# DRS4.net
KiCad netlist of a schematic drawn in Altium Designer
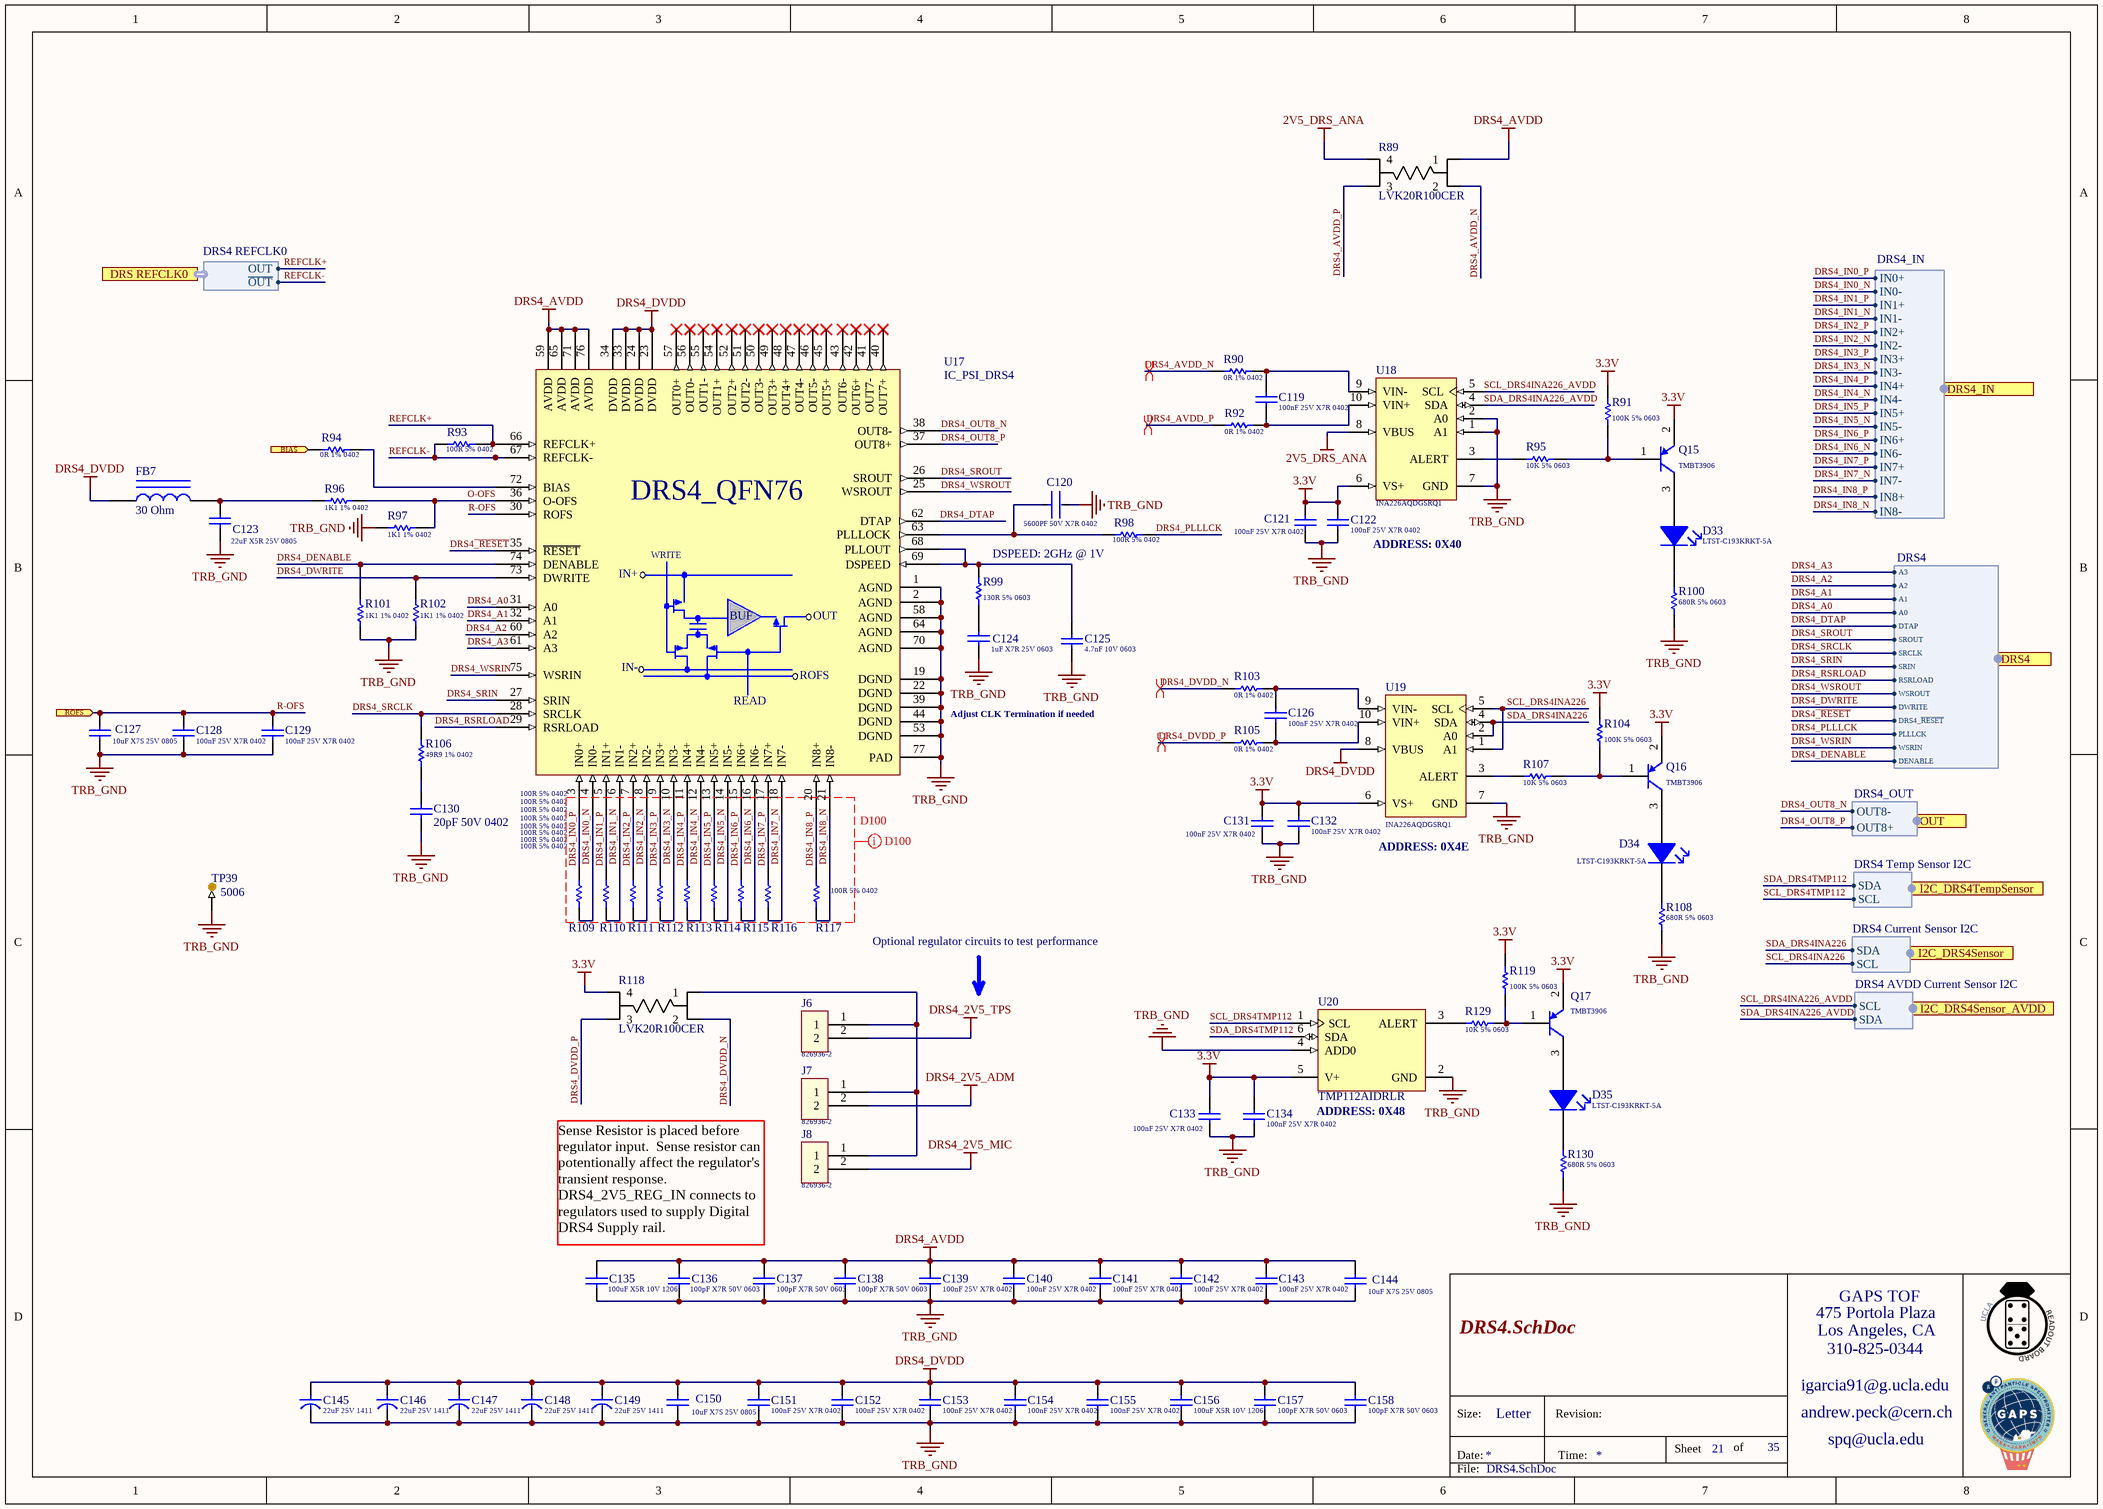
[diagram p0: DRS4.SchDoc]

(export (version "E")
  (design (tool "Eeschema 10.0.6"))
  (components
    (comp (ref "C119")
      (value "Cap_Taiyo_Yuden_TMK105B7104KV-FR_100nF")
      (footprint "Cap_Taiyo_Yuden_TMK105B7104KV-FR_100nF")
      (description "CAP CER 100nF 25V X7R 0402")
      (fields (field (name "CAPACITANCE") "100nF 25V X7R 0402"))
      (libsource (lib "Cap_Taiyo_Yuden_TMK105B7104KV-FR_100nF") (part "Cap_Taiyo_Yuden_TMK105B7104KV-FR_100nF"))
    )
    (comp (ref "C120")
      (value "5600PF 50V X7R 0402")
      (footprint "FP-C0402-BB-MFG")
      (description "CAP CER 5600PF 50V X7R 0402\r\nC0402C562K5RACTU")
      (fields (field (name "TOLERANCE") "0.1") (field (name "MANUFACTURER") "Kemet"))
      (libsource (lib "Altium Content Vault") (part "b4654b650e69147ec39a6b967a45e02"))
    )
    (comp (ref "C121")
      (value "Cap_Taiyo_Yuden_TMK105B7104KV-FR_100nF")
      (footprint "Cap_Taiyo_Yuden_TMK105B7104KV-FR_100nF")
      (description "CAP CER 100nF 25V X7R 0402")
      (fields (field (name "CAPACITANCE") "100nF 25V X7R 0402"))
      (libsource (lib "Cap_Taiyo_Yuden_TMK105B7104KV-FR_100nF") (part "Cap_Taiyo_Yuden_TMK105B7104KV-FR_100nF"))
    )
    (comp (ref "C122")
      (value "Cap_Taiyo_Yuden_TMK105B7104KV-FR_100nF")
      (footprint "Cap_Taiyo_Yuden_TMK105B7104KV-FR_100nF")
      (description "CAP CER 100nF 25V X7R 0402")
      (fields (field (name "CAPACITANCE") "100nF 25V X7R 0402"))
      (libsource (lib "Cap_Taiyo_Yuden_TMK105B7104KV-FR_100nF") (part "Cap_Taiyo_Yuden_TMK105B7104KV-FR_100nF"))
    )
    (comp (ref "C123")
      (value "Cap_Murata_GRT21BR61E226ME13L_22uF")
      (footprint "Cap_Murata_GRT21BR61E226ME13L_22uF")
      (description "CAP CER 22uF 25V X5R 0805")
      (fields (field (name "CAPACITANCE") "22uF X5R 25V 0805"))
      (libsource (lib "Cap_Murata_GRT21BR61E226ME13L_22uF") (part "Cap_Murata_GRT21BR61E226ME13L_22uF"))
    )
    (comp (ref "C124")
      (value "Cap_Murata_GCJ188R71E105KA01J_1uF")
      (footprint "Cap_Murata_GCJ188R71E105KA01J_1uF")
      (description "CAP CER 1uF 25V X7R 0603")
      (fields (field (name "CAPACITANCE") "1uF X7R 25V 0603"))
      (libsource (lib "Cap_Murata_GCJ188R71E105KA01J_1uF") (part "Cap_Murata_GCJ188R71E105KA01J_1uF"))
    )
    (comp (ref "C125")
      (value "4.7nF 10V 0603")
      (footprint "CAPC0603(1608)100_L")
      (description "CAP 4.7nF 10V ±10% 0603 (1608 Metric) Thickness 1mm SMD")
      (fields (field (name "TOLERANCE") "Â±10%"))
      (libsource (lib "Altium Content Vault") (part "CAP"))
    )
    (comp (ref "C126")
      (value "Cap_Taiyo_Yuden_TMK105B7104KV-FR_100nF")
      (footprint "Cap_Taiyo_Yuden_TMK105B7104KV-FR_100nF")
      (description "CAP CER 100nF 25V X7R 0402")
      (fields (field (name "CAPACITANCE") "100nF 25V X7R 0402"))
      (libsource (lib "Cap_Taiyo_Yuden_TMK105B7104KV-FR_100nF") (part "Cap_Taiyo_Yuden_TMK105B7104KV-FR_100nF"))
    )
    (comp (ref "C127")
      (value "Cap_Murata_ GRM21BC71E106ME11L_10uF")
      (footprint "Cap_Murata_ GRM21BC71E106ME11L_10uF")
      (description "CAP CER 10uF 25V X7R 0805")
      (fields (field (name "CAPACITANCE") "10uF X7S 25V 0805"))
      (libsource (lib "Cap_Murata_ GRM21BC71E106ME11L_10uF") (part "Cap_Murata_ GRM21BC71E106ME11L_10uF"))
    )
    (comp (ref "C128")
      (value "Cap_Taiyo_Yuden_TMK105B7104KV-FR_100nF")
      (footprint "Cap_Taiyo_Yuden_TMK105B7104KV-FR_100nF")
      (description "CAP CER 100nF 25V X7R 0402")
      (fields (field (name "CAPACITANCE") "100nF 25V X7R 0402"))
      (libsource (lib "Cap_Taiyo_Yuden_TMK105B7104KV-FR_100nF") (part "Cap_Taiyo_Yuden_TMK105B7104KV-FR_100nF"))
    )
    (comp (ref "C129")
      (value "Cap_Taiyo_Yuden_TMK105B7104KV-FR_100nF")
      (footprint "Cap_Taiyo_Yuden_TMK105B7104KV-FR_100nF")
      (description "CAP CER 100nF 25V X7R 0402")
      (fields (field (name "CAPACITANCE") "100nF 25V X7R 0402"))
      (libsource (lib "Cap_Taiyo_Yuden_TMK105B7104KV-FR_100nF") (part "Cap_Taiyo_Yuden_TMK105B7104KV-FR_100nF"))
    )
    (comp (ref "C130")
      (value "Cap_Murata_GJM1555C1H200GB01D_20pF")
      (footprint "Cap_Murata_GJM1555C1H200GB01D_20pF")
      (description "Multilayer Ceramic Capacitors MLCC - SMD/SMT 0402 20pF 50Volts C0G 2%")
      (fields (field (name "CAPACITANCE") "20pF 50V 0402"))
      (libsource (lib "Cap_Murata_GJM1555C1H200GB01D_20pF") (part "Cap_Murata_GJM1555C1H200GB01D_20pF"))
    )
    (comp (ref "C131")
      (value "Cap_Taiyo_Yuden_TMK105B7104KV-FR_100nF")
      (footprint "Cap_Taiyo_Yuden_TMK105B7104KV-FR_100nF")
      (description "CAP CER 100nF 25V X7R 0402")
      (fields (field (name "CAPACITANCE") "100nF 25V X7R 0402"))
      (libsource (lib "Cap_Taiyo_Yuden_TMK105B7104KV-FR_100nF") (part "Cap_Taiyo_Yuden_TMK105B7104KV-FR_100nF"))
    )
    (comp (ref "C132")
      (value "Cap_Taiyo_Yuden_TMK105B7104KV-FR_100nF")
      (footprint "Cap_Taiyo_Yuden_TMK105B7104KV-FR_100nF")
      (description "CAP CER 100nF 25V X7R 0402")
      (fields (field (name "CAPACITANCE") "100nF 25V X7R 0402"))
      (libsource (lib "Cap_Taiyo_Yuden_TMK105B7104KV-FR_100nF") (part "Cap_Taiyo_Yuden_TMK105B7104KV-FR_100nF"))
    )
    (comp (ref "C133")
      (value "Cap_Taiyo_Yuden_TMK105B7104KV-FR_100nF")
      (footprint "Cap_Taiyo_Yuden_TMK105B7104KV-FR_100nF")
      (description "CAP CER 100nF 25V X7R 0402")
      (fields (field (name "CAPACITANCE") "100nF 25V X7R 0402"))
      (libsource (lib "Cap_Taiyo_Yuden_TMK105B7104KV-FR_100nF") (part "Cap_Taiyo_Yuden_TMK105B7104KV-FR_100nF"))
    )
    (comp (ref "C134")
      (value "Cap_Taiyo_Yuden_TMK105B7104KV-FR_100nF")
      (footprint "Cap_Taiyo_Yuden_TMK105B7104KV-FR_100nF")
      (description "CAP CER 100nF 25V X7R 0402")
      (fields (field (name "CAPACITANCE") "100nF 25V X7R 0402"))
      (libsource (lib "Cap_Taiyo_Yuden_TMK105B7104KV-FR_100nF") (part "Cap_Taiyo_Yuden_TMK105B7104KV-FR_100nF"))
    )
    (comp (ref "C135")
      (value "Cap_Murata_GRM31CR61A107ME05L_100uF")
      (footprint "Cap_Murata_GRM31CR61A107ME05L_100uF")
      (description "CAP CER 100uF 25V X5R 1206")
      (fields (field (name "CAPACITANCE") "100uF X5R 10V 1206"))
      (libsource (lib "Cap_Murata_GRM31CR61A107ME05L_100uF") (part "Cap_Murata_GRM31CR61A107ME05L_100uF"))
    )
    (comp (ref "C136")
      (value "Cap_Kemet_C0603C101J5RACTU_100pF")
      (footprint "Cap_Kemet_C0603C101J5RACTU_100pF")
      (description "CAP CER 100pF 50V X7R 0603")
      (fields (field (name "CAPACITANCE") "100pF X7R 50V 0603"))
      (libsource (lib "Cap_Kemet_C0603C101J5RACTU_100pF") (part "Cap_Kemet_C0603C101J5RACTU_100pF"))
    )
    (comp (ref "C137")
      (value "Cap_Kemet_C0603C101J5RACTU_100pF")
      (footprint "Cap_Kemet_C0603C101J5RACTU_100pF")
      (description "CAP CER 100pF 50V X7R 0603")
      (fields (field (name "CAPACITANCE") "100pF X7R 50V 0603"))
      (libsource (lib "Cap_Kemet_C0603C101J5RACTU_100pF") (part "Cap_Kemet_C0603C101J5RACTU_100pF"))
    )
    (comp (ref "C138")
      (value "Cap_Kemet_C0603C101J5RACTU_100pF")
      (footprint "Cap_Kemet_C0603C101J5RACTU_100pF")
      (description "CAP CER 100pF 50V X7R 0603")
      (fields (field (name "CAPACITANCE") "100pF X7R 50V 0603"))
      (libsource (lib "Cap_Kemet_C0603C101J5RACTU_100pF") (part "Cap_Kemet_C0603C101J5RACTU_100pF"))
    )
    (comp (ref "C139")
      (value "Cap_Taiyo_Yuden_TMK105B7104KV-FR_100nF")
      (footprint "Cap_Taiyo_Yuden_TMK105B7104KV-FR_100nF")
      (description "CAP CER 100nF 25V X7R 0402")
      (fields (field (name "CAPACITANCE") "100nF 25V X7R 0402"))
      (libsource (lib "Cap_Taiyo_Yuden_TMK105B7104KV-FR_100nF") (part "Cap_Taiyo_Yuden_TMK105B7104KV-FR_100nF"))
    )
    (comp (ref "C140")
      (value "Cap_Taiyo_Yuden_TMK105B7104KV-FR_100nF")
      (footprint "Cap_Taiyo_Yuden_TMK105B7104KV-FR_100nF")
      (description "CAP CER 100nF 25V X7R 0402")
      (fields (field (name "CAPACITANCE") "100nF 25V X7R 0402"))
      (libsource (lib "Cap_Taiyo_Yuden_TMK105B7104KV-FR_100nF") (part "Cap_Taiyo_Yuden_TMK105B7104KV-FR_100nF"))
    )
    (comp (ref "C141")
      (value "Cap_Taiyo_Yuden_TMK105B7104KV-FR_100nF")
      (footprint "Cap_Taiyo_Yuden_TMK105B7104KV-FR_100nF")
      (description "CAP CER 100nF 25V X7R 0402")
      (fields (field (name "CAPACITANCE") "100nF 25V X7R 0402"))
      (libsource (lib "Cap_Taiyo_Yuden_TMK105B7104KV-FR_100nF") (part "Cap_Taiyo_Yuden_TMK105B7104KV-FR_100nF"))
    )
    (comp (ref "C142")
      (value "Cap_Taiyo_Yuden_TMK105B7104KV-FR_100nF")
      (footprint "Cap_Taiyo_Yuden_TMK105B7104KV-FR_100nF")
      (description "CAP CER 100nF 25V X7R 0402")
      (fields (field (name "CAPACITANCE") "100nF 25V X7R 0402"))
      (libsource (lib "Cap_Taiyo_Yuden_TMK105B7104KV-FR_100nF") (part "Cap_Taiyo_Yuden_TMK105B7104KV-FR_100nF"))
    )
    (comp (ref "C143")
      (value "Cap_Taiyo_Yuden_TMK105B7104KV-FR_100nF")
      (footprint "Cap_Taiyo_Yuden_TMK105B7104KV-FR_100nF")
      (description "CAP CER 100nF 25V X7R 0402")
      (fields (field (name "CAPACITANCE") "100nF 25V X7R 0402"))
      (libsource (lib "Cap_Taiyo_Yuden_TMK105B7104KV-FR_100nF") (part "Cap_Taiyo_Yuden_TMK105B7104KV-FR_100nF"))
    )
    (comp (ref "C144")
      (value "Cap_Murata_ GRM21BC71E106ME11L_10uF")
      (footprint "Cap_Murata_ GRM21BC71E106ME11L_10uF")
      (description "CAP CER 10uF 25V X7R 0805")
      (fields (field (name "CAPACITANCE") "10uF X7S 25V 0805"))
      (libsource (lib "Cap_Murata_ GRM21BC71E106ME11L_10uF") (part "Cap_Murata_ GRM21BC71E106ME11L_10uF"))
    )
    (comp (ref "C145")
      (value "Cap_Kemet_T521B226M025ATE100_22uF")
      (footprint "Cap_Kemet_T521B226M025ATE100_22uF")
      (description "Tantalum Capacitors - Polymer SMD 25V 22uF 1311 20% ESR=100mOhms")
      (fields (field (name "CAPACITANCE") "22uF 25V 1411"))
      (libsource (lib "Cap_Kemet_T521B226M025ATE100_22uF") (part "Cap_Kemet_T521B226M025ATE100_22uF"))
    )
    (comp (ref "C146")
      (value "Cap_Kemet_T521B226M025ATE100_22uF")
      (footprint "Cap_Kemet_T521B226M025ATE100_22uF")
      (description "Tantalum Capacitors - Polymer SMD 25V 22uF 1311 20% ESR=100mOhms")
      (fields (field (name "CAPACITANCE") "22uF 25V 1411"))
      (libsource (lib "Cap_Kemet_T521B226M025ATE100_22uF") (part "Cap_Kemet_T521B226M025ATE100_22uF"))
    )
    (comp (ref "C147")
      (value "Cap_Kemet_T521B226M025ATE100_22uF")
      (footprint "Cap_Kemet_T521B226M025ATE100_22uF")
      (description "Tantalum Capacitors - Polymer SMD 25V 22uF 1311 20% ESR=100mOhms")
      (fields (field (name "CAPACITANCE") "22uF 25V 1411"))
      (libsource (lib "Cap_Kemet_T521B226M025ATE100_22uF") (part "Cap_Kemet_T521B226M025ATE100_22uF"))
    )
    (comp (ref "C148")
      (value "Cap_Kemet_T521B226M025ATE100_22uF")
      (footprint "Cap_Kemet_T521B226M025ATE100_22uF")
      (description "Tantalum Capacitors - Polymer SMD 25V 22uF 1311 20% ESR=100mOhms")
      (fields (field (name "CAPACITANCE") "22uF 25V 1411"))
      (libsource (lib "Cap_Kemet_T521B226M025ATE100_22uF") (part "Cap_Kemet_T521B226M025ATE100_22uF"))
    )
    (comp (ref "C149")
      (value "Cap_Kemet_T521B226M025ATE100_22uF")
      (footprint "Cap_Kemet_T521B226M025ATE100_22uF")
      (description "Tantalum Capacitors - Polymer SMD 25V 22uF 1311 20% ESR=100mOhms")
      (fields (field (name "CAPACITANCE") "22uF 25V 1411"))
      (libsource (lib "Cap_Kemet_T521B226M025ATE100_22uF") (part "Cap_Kemet_T521B226M025ATE100_22uF"))
    )
    (comp (ref "C150")
      (value "Cap_Murata_ GRM21BC71E106ME11L_10uF")
      (footprint "Cap_Murata_ GRM21BC71E106ME11L_10uF")
      (description "CAP CER 10uF 25V X7R 0805")
      (fields (field (name "CAPACITANCE") "10uF X7S 25V 0805"))
      (libsource (lib "Cap_Murata_ GRM21BC71E106ME11L_10uF") (part "Cap_Murata_ GRM21BC71E106ME11L_10uF"))
    )
    (comp (ref "C151")
      (value "Cap_Taiyo_Yuden_TMK105B7104KV-FR_100nF")
      (footprint "Cap_Taiyo_Yuden_TMK105B7104KV-FR_100nF")
      (description "CAP CER 100nF 25V X7R 0402")
      (fields (field (name "CAPACITANCE") "100nF 25V X7R 0402"))
      (libsource (lib "Cap_Taiyo_Yuden_TMK105B7104KV-FR_100nF") (part "Cap_Taiyo_Yuden_TMK105B7104KV-FR_100nF"))
    )
    (comp (ref "C152")
      (value "Cap_Taiyo_Yuden_TMK105B7104KV-FR_100nF")
      (footprint "Cap_Taiyo_Yuden_TMK105B7104KV-FR_100nF")
      (description "CAP CER 100nF 25V X7R 0402")
      (fields (field (name "CAPACITANCE") "100nF 25V X7R 0402"))
      (libsource (lib "Cap_Taiyo_Yuden_TMK105B7104KV-FR_100nF") (part "Cap_Taiyo_Yuden_TMK105B7104KV-FR_100nF"))
    )
    (comp (ref "C153")
      (value "Cap_Taiyo_Yuden_TMK105B7104KV-FR_100nF")
      (footprint "Cap_Taiyo_Yuden_TMK105B7104KV-FR_100nF")
      (description "CAP CER 100nF 25V X7R 0402")
      (fields (field (name "CAPACITANCE") "100nF 25V X7R 0402"))
      (libsource (lib "Cap_Taiyo_Yuden_TMK105B7104KV-FR_100nF") (part "Cap_Taiyo_Yuden_TMK105B7104KV-FR_100nF"))
    )
    (comp (ref "C154")
      (value "Cap_Taiyo_Yuden_TMK105B7104KV-FR_100nF")
      (footprint "Cap_Taiyo_Yuden_TMK105B7104KV-FR_100nF")
      (description "CAP CER 100nF 25V X7R 0402")
      (fields (field (name "CAPACITANCE") "100nF 25V X7R 0402"))
      (libsource (lib "Cap_Taiyo_Yuden_TMK105B7104KV-FR_100nF") (part "Cap_Taiyo_Yuden_TMK105B7104KV-FR_100nF"))
    )
    (comp (ref "C155")
      (value "Cap_Taiyo_Yuden_TMK105B7104KV-FR_100nF")
      (footprint "Cap_Taiyo_Yuden_TMK105B7104KV-FR_100nF")
      (description "CAP CER 100nF 25V X7R 0402")
      (fields (field (name "CAPACITANCE") "100nF 25V X7R 0402"))
      (libsource (lib "Cap_Taiyo_Yuden_TMK105B7104KV-FR_100nF") (part "Cap_Taiyo_Yuden_TMK105B7104KV-FR_100nF"))
    )
    (comp (ref "C156")
      (value "Cap_Murata_GRM31CR61A107ME05L_100uF")
      (footprint "Cap_Murata_GRM31CR61A107ME05L_100uF")
      (description "CAP CER 100uF 25V X5R 1206")
      (fields (field (name "CAPACITANCE") "100uF X5R 10V 1206"))
      (libsource (lib "Cap_Murata_GRM31CR61A107ME05L_100uF") (part "Cap_Murata_GRM31CR61A107ME05L_100uF"))
    )
    (comp (ref "C157")
      (value "Cap_Kemet_C0603C101J5RACTU_100pF")
      (footprint "Cap_Kemet_C0603C101J5RACTU_100pF")
      (description "CAP CER 100pF 50V X7R 0603")
      (fields (field (name "CAPACITANCE") "100pF X7R 50V 0603"))
      (libsource (lib "Cap_Kemet_C0603C101J5RACTU_100pF") (part "Cap_Kemet_C0603C101J5RACTU_100pF"))
    )
    (comp (ref "C158")
      (value "Cap_Kemet_C0603C101J5RACTU_100pF")
      (footprint "Cap_Kemet_C0603C101J5RACTU_100pF")
      (description "CAP CER 100pF 50V X7R 0603")
      (fields (field (name "CAPACITANCE") "100pF X7R 50V 0603"))
      (libsource (lib "Cap_Kemet_C0603C101J5RACTU_100pF") (part "Cap_Kemet_C0603C101J5RACTU_100pF"))
    )
    (comp (ref "D33")
      (value "LTST-C193KRKT-5A")
      (footprint "Led_Lite-On_LTST-C193KGKT-5A_Red")
      (description "Standard LEDs - SMD Red 470nm 28mcd 20mA")
      (fields (field (name "SERIES") "LTST-C193KRKT-5A"))
      (libsource (lib "Led_Lite-On_LTST-C193KGKT-5A_Red") (part "Led_Lite-On_LTST-C193KGKT-5A_Red"))
    )
    (comp (ref "D34")
      (value "LTST-C193KRKT-5A")
      (footprint "Led_Lite-On_LTST-C193KGKT-5A_Red")
      (description "Standard LEDs - SMD Red 470nm 28mcd 20mA")
      (fields (field (name "SERIES") "LTST-C193KRKT-5A"))
      (libsource (lib "Led_Lite-On_LTST-C193KGKT-5A_Red") (part "Led_Lite-On_LTST-C193KGKT-5A_Red"))
    )
    (comp (ref "D35")
      (value "LTST-C193KRKT-5A")
      (footprint "Led_Lite-On_LTST-C193KGKT-5A_Red")
      (description "Standard LEDs - SMD Red 470nm 28mcd 20mA")
      (fields (field (name "SERIES") "LTST-C193KRKT-5A"))
      (libsource (lib "Led_Lite-On_LTST-C193KGKT-5A_Red") (part "Led_Lite-On_LTST-C193KGKT-5A_Red"))
    )
    (comp (ref "FB7")
      (value "30 Ohm")
      (footprint "Feb_MURATA_BLM15AX300SZ1D_30")
      (description "Feb SMD 30 OHM 25% 3/4W 0402")
      (libsource (lib "Feb_MURATA_BLM15AX300SZ1D_30") (part "Feb_MURATA_BLM15AX300SZ1D_30"))
    )
    (comp (ref "J6")
      (value "Header_TE_Connectivity_826936-2_2POS_5A")
      (footprint "Header_TE_Connectivity_826936-2_2POS_5A")
      (description "Headers & Wire Housings 2P SINGLE ROW 5A")
      (fields (field (name "SERIES") "826936-2"))
      (libsource (lib "Header_TE_Connectivity_826936-2_2POS_5A") (part "Header_TE_Connectivity_826936-2_2POS_5A"))
    )
    (comp (ref "J7")
      (value "Header_TE_Connectivity_826936-2_2POS_5A")
      (footprint "Header_TE_Connectivity_826936-2_2POS_5A")
      (description "Headers & Wire Housings 2P SINGLE ROW 5A")
      (fields (field (name "SERIES") "826936-2"))
      (libsource (lib "Header_TE_Connectivity_826936-2_2POS_5A") (part "Header_TE_Connectivity_826936-2_2POS_5A"))
    )
    (comp (ref "J8")
      (value "Header_TE_Connectivity_826936-2_2POS_5A")
      (footprint "Header_TE_Connectivity_826936-2_2POS_5A")
      (description "Headers & Wire Housings 2P SINGLE ROW 5A")
      (fields (field (name "SERIES") "826936-2"))
      (libsource (lib "Header_TE_Connectivity_826936-2_2POS_5A") (part "Header_TE_Connectivity_826936-2_2POS_5A"))
    )
    (comp (ref "Q15")
      (value "BJT_PNP_Toshiba_TMBT3906")
      (footprint "BJT_PNP_Toshiba_TMBT3906")
      (description "Bipolar Transistors - BJT Transistor for Low Freq. Amplification")
      (fields (field (name "SERIES") "TMBT3906") (field (name "MANUFACTURER") "Toshiba"))
      (libsource (lib "BJT_PNP_Toshiba_TMBT3906") (part "BJT_PNP_Toshiba_TMBT3906"))
    )
    (comp (ref "Q16")
      (value "BJT_PNP_Toshiba_TMBT3906")
      (footprint "BJT_PNP_Toshiba_TMBT3906")
      (description "Bipolar Transistors - BJT Transistor for Low Freq. Amplification")
      (fields (field (name "SERIES") "TMBT3906") (field (name "MANUFACTURER") "Toshiba"))
      (libsource (lib "BJT_PNP_Toshiba_TMBT3906") (part "BJT_PNP_Toshiba_TMBT3906"))
    )
    (comp (ref "Q17")
      (value "BJT_PNP_Toshiba_TMBT3906")
      (footprint "BJT_PNP_Toshiba_TMBT3906")
      (description "Bipolar Transistors - BJT Transistor for Low Freq. Amplification")
      (fields (field (name "SERIES") "TMBT3906") (field (name "MANUFACTURER") "Toshiba"))
      (libsource (lib "BJT_PNP_Toshiba_TMBT3906") (part "BJT_PNP_Toshiba_TMBT3906"))
    )
    (comp (ref "R89")
      (value "LVK20R100CER")
      (footprint "OH_LVK20_OHM")
      (description "Current Sense Resistors - SMD .1 OHM.25% 3/4W")
      (fields (field (name "COPYRIGHT") "Copyright (C) 2018 Accelerated Designs. All rights reserved"))
      (libsource (lib "Shunt_Res_Ohmite_LVK20R100CER") (part "LVK20R100CER"))
    )
    (comp (ref "R90")
      (value "Res_Vishay_CRCW04020000Z0EDC_0_Ohm")
      (footprint "Res_Vishay_CRCW04020000Z0EDC_0_Ohm")
      (description "0R 0.062W 1% 0402 (1005 Metric)  SMD")
      (fields (field (name "RESISTANCE") "0R 1% 0402"))
      (libsource (lib "Res_Vishay_CRCW04020000Z0EDC_0_Ohm") (part "Res_Vishay_CRCW04020000Z0EDC_0_Ohm"))
    )
    (comp (ref "R91")
      (value "100K 5% 0603")
      (footprint "RESC0603(1608)_N")
      (description "100K 0.1W 5% 0603 (1608 Metric)  SMD")
      (fields (field (name "TOLERANCE") "5 %") (field (name "POWER") "0.1 W"))
      (libsource (lib "Altium Content Vault") (part "RES"))
    )
    (comp (ref "R92")
      (value "Res_Vishay_CRCW04020000Z0EDC_0_Ohm")
      (footprint "Res_Vishay_CRCW04020000Z0EDC_0_Ohm")
      (description "0R 0.062W 1% 0402 (1005 Metric)  SMD")
      (fields (field (name "RESISTANCE") "0R 1% 0402"))
      (libsource (lib "Res_Vishay_CRCW04020000Z0EDC_0_Ohm") (part "Res_Vishay_CRCW04020000Z0EDC_0_Ohm"))
    )
    (comp (ref "R93")
      (value "100R 5% 0402")
      (footprint "RESC0402(1005)_L")
      (description "100R 0.063W 5% 0402 (1005 Metric)  SMD")
      (fields (field (name "TOLERANCE") "5 %") (field (name "POWER") "0.063 W"))
      (libsource (lib "Altium Content Vault") (part "RES"))
    )
    (comp (ref "R94")
      (value "Res_Vishay_CRCW04020000Z0EDC_0_Ohm")
      (footprint "Res_Vishay_CRCW04020000Z0EDC_0_Ohm")
      (description "0R 0.062W 1% 0402 (1005 Metric)  SMD")
      (fields (field (name "RESISTANCE") "0R 1% 0402"))
      (libsource (lib "Res_Vishay_CRCW04020000Z0EDC_0_Ohm") (part "Res_Vishay_CRCW04020000Z0EDC_0_Ohm"))
    )
    (comp (ref "R95")
      (value "10K 5% 0603")
      (footprint "RESC0603(1608)_L")
      (description "10K 0.1W 5% 0603 (1608 Metric)  SMD")
      (fields (field (name "TOLERANCE") "5 %") (field (name "POWER") "0.1 W"))
      (libsource (lib "Altium Content Vault") (part "RES"))
    )
    (comp (ref "R96")
      (value "1K1 1% 0402")
      (footprint "RESC0402(1005)_L")
      (description "1K1 0.063W 1% 0402 (1005 Metric)  SMD")
      (fields (field (name "POWER") "0.063 W") (field (name "TOLERANCE") "1 %"))
      (libsource (lib "Altium Content Vault") (part "RES"))
    )
    (comp (ref "R97")
      (value "1K1 1% 0402")
      (footprint "RESC0402(1005)_L")
      (description "1K1 0.063W 1% 0402 (1005 Metric)  SMD")
      (fields (field (name "POWER") "0.063 W") (field (name "TOLERANCE") "1 %"))
      (libsource (lib "Altium Content Vault") (part "RES"))
    )
    (comp (ref "R98")
      (value "100R 5% 0402")
      (footprint "RESC0402(1005)_L")
      (description "100R 0.063W 5% 0402 (1005 Metric)  SMD")
      (fields (field (name "TOLERANCE") "5 %") (field (name "POWER") "0.063 W"))
      (libsource (lib "Altium Content Vault") (part "RES"))
    )
    (comp (ref "R99")
      (value "130R 5% 0603")
      (footprint "RESC0603(1608)_L")
      (description "130R 0.1W 5% 0603 (1608 Metric)  SMD")
      (fields (field (name "TOLERANCE") "5 %") (field (name "POWER") "0.1 W"))
      (libsource (lib "Altium Content Vault") (part "RES"))
    )
    (comp (ref "R100")
      (value "680R 5% 0603")
      (footprint "RESC0603(1608)_L")
      (description "680R 0.1W 5% 0603 (1608 Metric)  SMD")
      (fields (field (name "TOLERANCE") "5 %") (field (name "POWER") "0.1 W"))
      (libsource (lib "Altium Content Vault") (part "RES"))
    )
    (comp (ref "R101")
      (value "1K1 1% 0402")
      (footprint "RESC0402(1005)_L")
      (description "1K1 0.063W 1% 0402 (1005 Metric)  SMD")
      (fields (field (name "POWER") "0.063 W") (field (name "TOLERANCE") "1 %"))
      (libsource (lib "Altium Content Vault") (part "RES"))
    )
    (comp (ref "R102")
      (value "1K1 1% 0402")
      (footprint "RESC0402(1005)_L")
      (description "1K1 0.063W 1% 0402 (1005 Metric)  SMD")
      (fields (field (name "POWER") "0.063 W") (field (name "TOLERANCE") "1 %"))
      (libsource (lib "Altium Content Vault") (part "RES"))
    )
    (comp (ref "R103")
      (value "Res_Vishay_CRCW04020000Z0EDC_0_Ohm")
      (footprint "Res_Vishay_CRCW04020000Z0EDC_0_Ohm")
      (description "0R 0.062W 1% 0402 (1005 Metric)  SMD")
      (fields (field (name "RESISTANCE") "0R 1% 0402"))
      (libsource (lib "Res_Vishay_CRCW04020000Z0EDC_0_Ohm") (part "Res_Vishay_CRCW04020000Z0EDC_0_Ohm"))
    )
    (comp (ref "R104")
      (value "100K 5% 0603")
      (footprint "RESC0603(1608)_N")
      (description "100K 0.1W 5% 0603 (1608 Metric)  SMD")
      (fields (field (name "TOLERANCE") "5 %") (field (name "POWER") "0.1 W"))
      (libsource (lib "Altium Content Vault") (part "RES"))
    )
    (comp (ref "R105")
      (value "Res_Vishay_CRCW04020000Z0EDC_0_Ohm")
      (footprint "Res_Vishay_CRCW04020000Z0EDC_0_Ohm")
      (description "0R 0.062W 1% 0402 (1005 Metric)  SMD")
      (fields (field (name "RESISTANCE") "0R 1% 0402"))
      (libsource (lib "Res_Vishay_CRCW04020000Z0EDC_0_Ohm") (part "Res_Vishay_CRCW04020000Z0EDC_0_Ohm"))
    )
    (comp (ref "R106")
      (value "49R9 1% 0402")
      (footprint "RESC0402(1005)_L")
      (description "49R9 0.063W 1% 0402 (1005 Metric)  SMD")
      (fields (field (name "POWER") "0.063 W") (field (name "TOLERANCE") "1 %"))
      (libsource (lib "Altium Content Vault") (part "RES"))
    )
    (comp (ref "R107")
      (value "10K 5% 0603")
      (footprint "RESC0603(1608)_L")
      (description "10K 0.1W 5% 0603 (1608 Metric)  SMD")
      (fields (field (name "TOLERANCE") "5 %") (field (name "POWER") "0.1 W"))
      (libsource (lib "Altium Content Vault") (part "RES"))
    )
    (comp (ref "R108")
      (value "680R 5% 0603")
      (footprint "RESC0603(1608)_L")
      (description "680R 0.1W 5% 0603 (1608 Metric)  SMD")
      (fields (field (name "TOLERANCE") "5 %") (field (name "POWER") "0.1 W"))
      (libsource (lib "Altium Content Vault") (part "RES"))
    )
    (comp (ref "R109")
      (value "100R 5% 0402")
      (footprint "RESC0402(1005)_L")
      (description "100R 0.063W 5% 0402 (1005 Metric)  SMD")
      (fields (field (name "TOLERANCE") "5 %") (field (name "POWER") "0.063 W"))
      (libsource (lib "Altium Content Vault") (part "RES"))
    )
    (comp (ref "R110")
      (value "100R 5% 0402")
      (footprint "RESC0402(1005)_L")
      (description "100R 0.063W 5% 0402 (1005 Metric)  SMD")
      (fields (field (name "TOLERANCE") "5 %") (field (name "POWER") "0.063 W"))
      (libsource (lib "Altium Content Vault") (part "RES"))
    )
    (comp (ref "R111")
      (value "100R 5% 0402")
      (footprint "RESC0402(1005)_L")
      (description "100R 0.063W 5% 0402 (1005 Metric)  SMD")
      (fields (field (name "TOLERANCE") "5 %") (field (name "POWER") "0.063 W"))
      (libsource (lib "Altium Content Vault") (part "RES"))
    )
    (comp (ref "R112")
      (value "100R 5% 0402")
      (footprint "RESC0402(1005)_L")
      (description "100R 0.063W 5% 0402 (1005 Metric)  SMD")
      (fields (field (name "TOLERANCE") "5 %") (field (name "POWER") "0.063 W"))
      (libsource (lib "Altium Content Vault") (part "RES"))
    )
    (comp (ref "R113")
      (value "100R 5% 0402")
      (footprint "RESC0402(1005)_L")
      (description "100R 0.063W 5% 0402 (1005 Metric)  SMD")
      (fields (field (name "TOLERANCE") "5 %") (field (name "POWER") "0.063 W"))
      (libsource (lib "Altium Content Vault") (part "RES"))
    )
    (comp (ref "R114")
      (value "100R 5% 0402")
      (footprint "RESC0402(1005)_L")
      (description "100R 0.063W 5% 0402 (1005 Metric)  SMD")
      (fields (field (name "TOLERANCE") "5 %") (field (name "POWER") "0.063 W"))
      (libsource (lib "Altium Content Vault") (part "RES"))
    )
    (comp (ref "R115")
      (value "100R 5% 0402")
      (footprint "RESC0402(1005)_L")
      (description "100R 0.063W 5% 0402 (1005 Metric)  SMD")
      (fields (field (name "TOLERANCE") "5 %") (field (name "POWER") "0.063 W"))
      (libsource (lib "Altium Content Vault") (part "RES"))
    )
    (comp (ref "R116")
      (value "100R 5% 0402")
      (footprint "RESC0402(1005)_L")
      (description "100R 0.063W 5% 0402 (1005 Metric)  SMD")
      (fields (field (name "TOLERANCE") "5 %") (field (name "POWER") "0.063 W"))
      (libsource (lib "Altium Content Vault") (part "RES"))
    )
    (comp (ref "R117")
      (value "100R 5% 0402")
      (footprint "RESC0402(1005)_L")
      (description "100R 0.063W 5% 0402 (1005 Metric)  SMD")
      (fields (field (name "TOLERANCE") "5 %") (field (name "POWER") "0.063 W"))
      (libsource (lib "Altium Content Vault") (part "RES"))
    )
    (comp (ref "R118")
      (value "LVK20R100CER")
      (footprint "OH_LVK20_OHM")
      (description "Current Sense Resistors - SMD .1 OHM.25% 3/4W")
      (fields (field (name "COPYRIGHT") "Copyright (C) 2018 Accelerated Designs. All rights reserved"))
      (libsource (lib "Shunt_Res_Ohmite_LVK20R100CER") (part "LVK20R100CER"))
    )
    (comp (ref "R119")
      (value "100K 5% 0603")
      (footprint "RESC0603(1608)_N")
      (description "100K 0.1W 5% 0603 (1608 Metric)  SMD")
      (fields (field (name "TOLERANCE") "5 %") (field (name "POWER") "0.1 W"))
      (libsource (lib "Altium Content Vault") (part "RES"))
    )
    (comp (ref "R129")
      (value "10K 5% 0603")
      (footprint "RESC0603(1608)_L")
      (description "10K 0.1W 5% 0603 (1608 Metric)  SMD")
      (fields (field (name "TOLERANCE") "5 %") (field (name "POWER") "0.1 W"))
      (libsource (lib "Altium Content Vault") (part "RES"))
    )
    (comp (ref "R130")
      (value "680R 5% 0603")
      (footprint "RESC0603(1608)_L")
      (description "680R 0.1W 5% 0603 (1608 Metric)  SMD")
      (fields (field (name "TOLERANCE") "5 %") (field (name "POWER") "0.1 W"))
      (libsource (lib "Altium Content Vault") (part "RES"))
    )
    (comp (ref "TP39")
      (value "TP_Keystone_Electronics_5006")
      (footprint "TP_Keystone_Electronics_5006")
      (description "Circuit Board Hardware - PCB TEST POINT BLK .063")
      (fields (field (name "SERIES") "5006"))
      (libsource (lib "TP_Keystone_Electronics_5006") (part "TP_Keystone_Electronics_5006"))
    )
    (comp (ref "U17")
      (value "IC_PSI_DRS4")
      (footprint "DRS4")
      (description "DRS4 QFN76 DAQ Chip")
      (libsource (lib "DRS4_V09") (part "DRS4"))
    )
    (comp (ref "U18")
      (value "INA226AQDGSRQ1")
      (footprint "INA226AQDGSRQ1")
      (libsource (lib "INA226AQDGSRQ1") (part "INA226AQDGSRQ1"))
    )
    (comp (ref "U19")
      (value "INA226AQDGSRQ1")
      (footprint "INA226AQDGSRQ1")
      (libsource (lib "INA226AQDGSRQ1") (part "INA226AQDGSRQ1"))
    )
    (comp (ref "U20")
      (value "TMP112AIDRLR")
      (footprint "TMP112AIDRLR")
      (description "Board Mount Temperature Sensors Hi-Prec Lo-Pwr Dig Temp Sensor")
      (libsource (lib "TMP112AIDRLR") (part "TMP112AIDRLR"))
    )
  )
  (nets
    (net (code "10") (name "/BIAS") (class "Default")
      (node (ref "R94") (pin "1") (pinfunction "1_1") (pintype "passive"))
    )
    (net (code "11") (name "/DRS4_A0") (class "Default")
      (node (ref "U17") (pin "31") (pinfunction "A0_31") (pintype "input"))
    )
    (net (code "12") (name "/DRS4_A1") (class "Default")
      (node (ref "U17") (pin "32") (pinfunction "A1_32") (pintype "input"))
    )
    (net (code "13") (name "/DRS4_A2") (class "Default")
      (node (ref "U17") (pin "60") (pinfunction "A2_60") (pintype "input"))
    )
    (net (code "14") (name "/DRS4_A3") (class "Default")
      (node (ref "U17") (pin "61") (pinfunction "A3_61") (pintype "input"))
    )
    (net (code "15") (name "/DRS4_AVDD_N") (class "Default")
      (node (ref "R89") (pin "2") (pinfunction "2_2") (pintype "passive"))
      (node (ref "R90") (pin "1") (pinfunction "1_1") (pintype "passive"))
    )
    (net (code "16") (name "/DRS4_AVDD_P") (class "Default")
      (node (ref "R89") (pin "3") (pinfunction "3_3") (pintype "passive"))
      (node (ref "R92") (pin "1") (pinfunction "1_1") (pintype "passive"))
    )
    (net (code "17") (name "/DRS4_DENABLE") (class "Default")
      (node (ref "R101") (pin "2") (pinfunction "2_2") (pintype "passive"))
      (node (ref "U17") (pin "74") (pinfunction "DENABLE_74") (pintype "input"))
    )
    (net (code "18") (name "/DRS4_DTAP") (class "Default")
      (node (ref "U17") (pin "62") (pinfunction "DTAP_62") (pintype "output"))
    )
    (net (code "19") (name "/DRS4_DVDD_N") (class "Default")
      (node (ref "R103") (pin "1") (pinfunction "1_1") (pintype "passive"))
      (node (ref "R118") (pin "2") (pinfunction "2_2") (pintype "passive"))
    )
    (net (code "20") (name "/DRS4_DVDD_P") (class "Default")
      (node (ref "R105") (pin "1") (pinfunction "1_1") (pintype "passive"))
      (node (ref "R118") (pin "3") (pinfunction "3_3") (pintype "passive"))
    )
    (net (code "21") (name "/DRS4_DWRITE") (class "Default")
      (node (ref "R102") (pin "2") (pinfunction "2_2") (pintype "passive"))
      (node (ref "U17") (pin "73") (pinfunction "DWRITE_73") (pintype "input"))
    )
    (net (code "22") (name "/DRS4_IN0_N") (class "Default")
      (node (ref "R109") (pin "2") (pinfunction "2_2") (pintype "passive"))
      (node (ref "U17") (pin "4") (pinfunction "IN0-_4") (pintype "input"))
    )
    (net (code "23") (name "/DRS4_IN0_P") (class "Default")
      (node (ref "R109") (pin "1") (pinfunction "1_1") (pintype "passive"))
      (node (ref "U17") (pin "3") (pinfunction "IN0+_3") (pintype "input"))
    )
    (net (code "24") (name "/DRS4_IN1_N") (class "Default")
      (node (ref "R110") (pin "2") (pinfunction "2_2") (pintype "passive"))
      (node (ref "U17") (pin "6") (pinfunction "IN1-_6") (pintype "input"))
    )
    (net (code "25") (name "/DRS4_IN1_P") (class "Default")
      (node (ref "R110") (pin "1") (pinfunction "1_1") (pintype "passive"))
      (node (ref "U17") (pin "5") (pinfunction "IN1+_5") (pintype "input"))
    )
    (net (code "26") (name "/DRS4_IN2_N") (class "Default")
      (node (ref "R111") (pin "2") (pinfunction "2_2") (pintype "passive"))
      (node (ref "U17") (pin "8") (pinfunction "IN2-_8") (pintype "input"))
    )
    (net (code "27") (name "/DRS4_IN2_P") (class "Default")
      (node (ref "R111") (pin "1") (pinfunction "1_1") (pintype "passive"))
      (node (ref "U17") (pin "7") (pinfunction "IN2+_7") (pintype "input"))
    )
    (net (code "28") (name "/DRS4_IN3_N") (class "Default")
      (node (ref "R112") (pin "2") (pinfunction "2_2") (pintype "passive"))
      (node (ref "U17") (pin "10") (pinfunction "IN3-_10") (pintype "input"))
    )
    (net (code "29") (name "/DRS4_IN3_P") (class "Default")
      (node (ref "R112") (pin "1") (pinfunction "1_1") (pintype "passive"))
      (node (ref "U17") (pin "9") (pinfunction "IN3+_9") (pintype "input"))
    )
    (net (code "30") (name "/DRS4_IN4_N") (class "Default")
      (node (ref "R113") (pin "2") (pinfunction "2_2") (pintype "passive"))
      (node (ref "U17") (pin "12") (pinfunction "IN4-_12") (pintype "input"))
    )
    (net (code "31") (name "/DRS4_IN4_P") (class "Default")
      (node (ref "R113") (pin "1") (pinfunction "1_1") (pintype "passive"))
      (node (ref "U17") (pin "11") (pinfunction "IN4+_11") (pintype "input"))
    )
    (net (code "32") (name "/DRS4_IN5_N") (class "Default")
      (node (ref "R114") (pin "2") (pinfunction "2_2") (pintype "passive"))
      (node (ref "U17") (pin "14") (pinfunction "IN5-_14") (pintype "input"))
    )
    (net (code "33") (name "/DRS4_IN5_P") (class "Default")
      (node (ref "R114") (pin "1") (pinfunction "1_1") (pintype "passive"))
      (node (ref "U17") (pin "13") (pinfunction "IN5+_13") (pintype "input"))
    )
    (net (code "34") (name "/DRS4_IN6_N") (class "Default")
      (node (ref "R115") (pin "2") (pinfunction "2_2") (pintype "passive"))
      (node (ref "U17") (pin "16") (pinfunction "IN6-_16") (pintype "input"))
    )
    (net (code "35") (name "/DRS4_IN6_P") (class "Default")
      (node (ref "R115") (pin "1") (pinfunction "1_1") (pintype "passive"))
      (node (ref "U17") (pin "15") (pinfunction "IN6+_15") (pintype "input"))
    )
    (net (code "36") (name "/DRS4_IN7_N") (class "Default")
      (node (ref "R116") (pin "2") (pinfunction "2_2") (pintype "passive"))
      (node (ref "U17") (pin "18") (pinfunction "IN7-_18") (pintype "input"))
    )
    (net (code "37") (name "/DRS4_IN7_P") (class "Default")
      (node (ref "R116") (pin "1") (pinfunction "1_1") (pintype "passive"))
      (node (ref "U17") (pin "17") (pinfunction "IN7+_17") (pintype "input"))
    )
    (net (code "38") (name "/DRS4_IN8_N") (class "Default")
      (node (ref "R117") (pin "2") (pinfunction "2_2") (pintype "passive"))
      (node (ref "U17") (pin "21") (pinfunction "IN8-_21") (pintype "input"))
    )
    (net (code "39") (name "/DRS4_IN8_P") (class "Default")
      (node (ref "R117") (pin "1") (pinfunction "1_1") (pintype "passive"))
      (node (ref "U17") (pin "20") (pinfunction "IN8+_20") (pintype "input"))
    )
    (net (code "40") (name "/DRS4_OUT8_N") (class "Default")
      (node (ref "U17") (pin "38") (pinfunction "OUT8-_38") (pintype "output"))
    )
    (net (code "41") (name "/DRS4_OUT8_P") (class "Default")
      (node (ref "U17") (pin "37") (pinfunction "OUT8+_37") (pintype "output"))
    )
    (net (code "42") (name "/DRS4_PLLLCK") (class "Default")
      (node (ref "R98") (pin "1") (pinfunction "1_1") (pintype "passive"))
    )
    (net (code "43") (name "/DRS4_RSRLOAD") (class "Default")
      (node (ref "U17") (pin "29") (pinfunction "RSRLOAD_29") (pintype "input"))
    )
    (net (code "44") (name "/DRS4_SRCLK") (class "Default")
      (node (ref "R106") (pin "1") (pinfunction "1_1") (pintype "passive"))
      (node (ref "U17") (pin "28") (pinfunction "SRCLK_28") (pintype "input"))
    )
    (net (code "45") (name "/DRS4_SRIN") (class "Default")
      (node (ref "U17") (pin "27") (pinfunction "SRIN_27") (pintype "input"))
    )
    (net (code "46") (name "/DRS4_SROUT") (class "Default")
      (node (ref "U17") (pin "26") (pinfunction "SROUT_26") (pintype "output"))
    )
    (net (code "47") (name "/DRS4_WSRIN") (class "Default")
      (node (ref "U17") (pin "75") (pinfunction "WSRIN_75") (pintype "input"))
    )
    (net (code "48") (name "/DRS4_WSROUT") (class "Default")
      (node (ref "U17") (pin "25") (pinfunction "WSROUT_25") (pintype "output"))
    )
    (net (code "49") (name "/DRS4~{_RESET}") (class "Default")
      (node (ref "U17") (pin "35") (pinfunction "~{RESET}_35") (pintype "input"))
    )
    (net (code "50") (name "/O-OFS") (class "Default")
      (node (ref "R96") (pin "1") (pinfunction "1_1") (pintype "passive"))
      (node (ref "R97") (pin "1") (pinfunction "1_1") (pintype "passive"))
      (node (ref "U17") (pin "36") (pinfunction "O-OFS_36") (pintype "input"))
    )
    (net (code "51") (name "/R-OFS") (class "Default")
      (node (ref "C127") (pin "1") (pinfunction "1_1") (pintype "passive"))
      (node (ref "C128") (pin "2") (pinfunction "2_2") (pintype "passive"))
      (node (ref "C129") (pin "2") (pinfunction "2_2") (pintype "passive"))
      (node (ref "U17") (pin "30") (pinfunction "ROFS_30") (pintype "input"))
    )
    (net (code "52") (name "/REFCLK+") (class "Default")
      (node (ref "R93") (pin "1") (pinfunction "1_1") (pintype "passive"))
      (node (ref "U17") (pin "66") (pinfunction "REFCLK+_66") (pintype "input"))
    )
    (net (code "53") (name "/REFCLK-") (class "Default")
      (node (ref "R93") (pin "2") (pinfunction "2_2") (pintype "passive"))
      (node (ref "U17") (pin "67") (pinfunction "REFCLK-_67") (pintype "input"))
    )
    (net (code "54") (name "/SCL_DRS4INA226") (class "Default")
      (node (ref "U19") (pin "1") (pinfunction "A1_1") (pintype "input"))
      (node (ref "U19") (pin "5") (pinfunction "SCL_5") (pintype "input"))
    )
    (net (code "55") (name "/SCL_DRS4INA226_AVDD") (class "Default")
      (node (ref "U18") (pin "5") (pinfunction "SCL_5") (pintype "input"))
    )
    (net (code "56") (name "/SCL_DRS4TMP112") (class "Default")
      (node (ref "U20") (pin "1") (pinfunction "SCL_1") (pintype "input"))
    )
    (net (code "57") (name "/SDA_DRS4INA226") (class "Default")
      (node (ref "U19") (pin "2") (pinfunction "A0_2") (pintype "input"))
      (node (ref "U19") (pin "4") (pinfunction "SDA_4") (pintype "bidirectional"))
    )
    (net (code "58") (name "/SDA_DRS4INA226_AVDD") (class "Default")
      (node (ref "U18") (pin "4") (pinfunction "SDA_4") (pintype "bidirectional"))
    )
    (net (code "59") (name "/SDA_DRS4TMP112") (class "Default")
      (node (ref "U20") (pin "6") (pinfunction "SDA_6") (pintype "bidirectional"))
    )
    (net (code "67") (name "2V5_DRS_ANA") (class "Default")
      (node (ref "R89") (pin "4") (pinfunction "4_4") (pintype "power_in"))
      (node (ref "U18") (pin "8") (pinfunction "VBUS_8") (pintype "input"))
    )
    (net (code "68") (name "3.3V") (class "Default")
      (node (ref "C121") (pin "2") (pinfunction "2_2") (pintype "passive"))
      (node (ref "C122") (pin "2") (pinfunction "2_2") (pintype "passive"))
      (node (ref "C131") (pin "2") (pinfunction "2_2") (pintype "passive"))
      (node (ref "C132") (pin "2") (pinfunction "2_2") (pintype "passive"))
      (node (ref "C133") (pin "2") (pinfunction "2_2") (pintype "passive"))
      (node (ref "C134") (pin "2") (pinfunction "2_2") (pintype "passive"))
      (node (ref "Q15") (pin "2") (pinfunction "E_2") (pintype "passive"))
      (node (ref "Q16") (pin "2") (pinfunction "E_2") (pintype "passive"))
      (node (ref "Q17") (pin "2") (pinfunction "E_2") (pintype "passive"))
      (node (ref "R104") (pin "2") (pinfunction "2_2") (pintype "passive"))
      (node (ref "R118") (pin "4") (pinfunction "4_4") (pintype "power_in"))
      (node (ref "R119") (pin "2") (pinfunction "2_2") (pintype "passive"))
      (node (ref "R91") (pin "2") (pinfunction "2_2") (pintype "passive"))
      (node (ref "U18") (pin "6") (pinfunction "VS+_6") (pintype "input"))
      (node (ref "U19") (pin "6") (pinfunction "VS+_6") (pintype "input"))
      (node (ref "U20") (pin "5") (pinfunction "V+_5") (pintype "power_in"))
    )
    (net (code "69") (name "DRS4_2V5_ADM") (class "Default")
      (node (ref "J7") (pin "2") (pinfunction "2_2") (pintype "passive"))
    )
    (net (code "70") (name "DRS4_2V5_MIC") (class "Default")
      (node (ref "J8") (pin "2") (pinfunction "2_2") (pintype "passive"))
    )
    (net (code "71") (name "DRS4_2V5_TPS") (class "Default")
      (node (ref "J6") (pin "2") (pinfunction "2_2") (pintype "passive"))
    )
    (net (code "72") (name "DRS4_AVDD") (class "Default")
      (node (ref "C135") (pin "2") (pinfunction "2_2") (pintype "passive"))
      (node (ref "C136") (pin "1") (pinfunction "1_1") (pintype "passive"))
      (node (ref "C137") (pin "1") (pinfunction "1_1") (pintype "passive"))
      (node (ref "C138") (pin "1") (pinfunction "1_1") (pintype "passive"))
      (node (ref "C139") (pin "2") (pinfunction "2_2") (pintype "passive"))
      (node (ref "C140") (pin "2") (pinfunction "2_2") (pintype "passive"))
      (node (ref "C141") (pin "2") (pinfunction "2_2") (pintype "passive"))
      (node (ref "C142") (pin "2") (pinfunction "2_2") (pintype "passive"))
      (node (ref "C143") (pin "2") (pinfunction "2_2") (pintype "passive"))
      (node (ref "C144") (pin "1") (pinfunction "1_1") (pintype "passive"))
      (node (ref "R89") (pin "1") (pinfunction "1_1") (pintype "power_in"))
      (node (ref "U17") (pin "59") (pinfunction "AVDD_59") (pintype "power_in"))
      (node (ref "U17") (pin "65") (pinfunction "AVDD_65") (pintype "power_in"))
      (node (ref "U17") (pin "71") (pinfunction "AVDD_71") (pintype "power_in"))
      (node (ref "U17") (pin "76") (pinfunction "AVDD_76") (pintype "power_in"))
    )
    (net (code "73") (name "DRS4_DVDD") (class "Default")
      (node (ref "C145") (pin "1") (pinfunction "1_1") (pintype "passive"))
      (node (ref "C146") (pin "1") (pinfunction "1_1") (pintype "passive"))
      (node (ref "C147") (pin "1") (pinfunction "1_1") (pintype "passive"))
      (node (ref "C148") (pin "1") (pinfunction "1_1") (pintype "passive"))
      (node (ref "C149") (pin "1") (pinfunction "1_1") (pintype "passive"))
      (node (ref "C150") (pin "1") (pinfunction "1_1") (pintype "passive"))
      (node (ref "C151") (pin "2") (pinfunction "2_2") (pintype "passive"))
      (node (ref "C152") (pin "2") (pinfunction "2_2") (pintype "passive"))
      (node (ref "C153") (pin "2") (pinfunction "2_2") (pintype "passive"))
      (node (ref "C154") (pin "2") (pinfunction "2_2") (pintype "passive"))
      (node (ref "C155") (pin "2") (pinfunction "2_2") (pintype "passive"))
      (node (ref "C156") (pin "2") (pinfunction "2_2") (pintype "passive"))
      (node (ref "C157") (pin "1") (pinfunction "1_1") (pintype "passive"))
      (node (ref "C158") (pin "1") (pinfunction "1_1") (pintype "passive"))
      (node (ref "FB7") (pin "1") (pinfunction "1_1") (pintype "passive"))
      (node (ref "U17") (pin "23") (pinfunction "DVDD_23") (pintype "power_in"))
      (node (ref "U17") (pin "24") (pinfunction "DVDD_24") (pintype "power_in"))
      (node (ref "U17") (pin "33") (pinfunction "DVDD_33") (pintype "power_in"))
      (node (ref "U17") (pin "34") (pinfunction "DVDD_34") (pintype "power_in"))
      (node (ref "U19") (pin "8") (pinfunction "VBUS_8") (pintype "input"))
    )
    (net (code "74") (name "Net-(C123-Pad2)") (class "Default")
      (node (ref "C123") (pin "2") (pinfunction "2_2") (pintype "passive"))
      (node (ref "FB7") (pin "2") (pinfunction "2_2") (pintype "passive"))
      (node (ref "R96") (pin "2") (pinfunction "2_2") (pintype "passive"))
    )
    (net (code "75") (name "Net-(C124-Pad2)") (class "Default")
      (node (ref "C124") (pin "2") (pinfunction "2_2") (pintype "passive"))
      (node (ref "R99") (pin "1") (pinfunction "1_1") (pintype "passive"))
    )
    (net (code "76") (name "Net-(C130-Pad2)") (class "Default")
      (node (ref "C130") (pin "2") (pinfunction "2_2") (pintype "passive"))
      (node (ref "R106") (pin "2") (pinfunction "2_2") (pintype "passive"))
    )
    (net (code "77") (name "Net-(D33-A)") (class "Default")
      (node (ref "D33") (pin "2") (pinfunction "A_2") (pintype "passive"))
      (node (ref "Q15") (pin "3") (pinfunction "C_3") (pintype "passive"))
    )
    (net (code "78") (name "Net-(D33-K)") (class "Default")
      (node (ref "D33") (pin "1") (pinfunction "K_1") (pintype "passive"))
      (node (ref "R100") (pin "2") (pinfunction "2_2") (pintype "passive"))
    )
    (net (code "79") (name "Net-(D34-A)") (class "Default")
      (node (ref "D34") (pin "2") (pinfunction "A_2") (pintype "passive"))
      (node (ref "Q16") (pin "3") (pinfunction "C_3") (pintype "passive"))
    )
    (net (code "80") (name "Net-(D34-K)") (class "Default")
      (node (ref "D34") (pin "1") (pinfunction "K_1") (pintype "passive"))
      (node (ref "R108") (pin "2") (pinfunction "2_2") (pintype "passive"))
    )
    (net (code "81") (name "Net-(D35-A)") (class "Default")
      (node (ref "D35") (pin "2") (pinfunction "A_2") (pintype "passive"))
      (node (ref "Q17") (pin "3") (pinfunction "C_3") (pintype "passive"))
    )
    (net (code "82") (name "Net-(D35-K)") (class "Default")
      (node (ref "D35") (pin "1") (pinfunction "K_1") (pintype "passive"))
      (node (ref "R130") (pin "2") (pinfunction "2_2") (pintype "passive"))
    )
    (net (code "83") (name "Net-(J6-Pad1)") (class "Default")
      (node (ref "J6") (pin "1") (pinfunction "1_1") (pintype "passive"))
      (node (ref "J7") (pin "1") (pinfunction "1_1") (pintype "passive"))
      (node (ref "J8") (pin "1") (pinfunction "1_1") (pintype "passive"))
      (node (ref "R118") (pin "1") (pinfunction "1_1") (pintype "power_in"))
    )
    (net (code "84") (name "Net-(Q15-B)") (class "Default")
      (node (ref "Q15") (pin "1") (pinfunction "B_1") (pintype "passive"))
      (node (ref "R91") (pin "1") (pinfunction "1_1") (pintype "passive"))
      (node (ref "R95") (pin "1") (pinfunction "1_1") (pintype "passive"))
    )
    (net (code "85") (name "Net-(Q16-B)") (class "Default")
      (node (ref "Q16") (pin "1") (pinfunction "B_1") (pintype "passive"))
      (node (ref "R104") (pin "1") (pinfunction "1_1") (pintype "passive"))
      (node (ref "R107") (pin "1") (pinfunction "1_1") (pintype "passive"))
    )
    (net (code "86") (name "Net-(Q17-B)") (class "Default")
      (node (ref "Q17") (pin "1") (pinfunction "B_1") (pintype "passive"))
      (node (ref "R119") (pin "1") (pinfunction "1_1") (pintype "passive"))
      (node (ref "R129") (pin "1") (pinfunction "1_1") (pintype "passive"))
    )
    (net (code "87") (name "Net-(U17-BIAS)") (class "Default")
      (node (ref "R94") (pin "2") (pinfunction "2_2") (pintype "passive"))
      (node (ref "U17") (pin "72") (pinfunction "BIAS_72") (pintype "input"))
    )
    (net (code "88") (name "Net-(U17-DSPEED)") (class "Default")
      (node (ref "C125") (pin "2") (pinfunction "2_2") (pintype "passive"))
      (node (ref "R99") (pin "2") (pinfunction "2_2") (pintype "passive"))
      (node (ref "U17") (pin "68") (pinfunction "PLLOUT_68") (pintype "output"))
      (node (ref "U17") (pin "69") (pinfunction "DSPEED_69") (pintype "input"))
    )
    (net (code "89") (name "Net-(U17-PLLLOCK)") (class "Default")
      (node (ref "C120") (pin "1") (pinfunction "1_1") (pintype "passive"))
      (node (ref "R98") (pin "2") (pinfunction "2_2") (pintype "passive"))
      (node (ref "U17") (pin "63") (pinfunction "PLLLOCK_63") (pintype "output"))
    )
    (net (code "90") (name "Net-(U18-ALERT)") (class "Default")
      (node (ref "R95") (pin "2") (pinfunction "2_2") (pintype "passive"))
      (node (ref "U18") (pin "3") (pinfunction "ALERT_3") (pintype "open_collector"))
    )
    (net (code "91") (name "Net-(U18-VIN+)") (class "Default")
      (node (ref "C119") (pin "1") (pinfunction "1_1") (pintype "passive"))
      (node (ref "R92") (pin "2") (pinfunction "2_2") (pintype "passive"))
      (node (ref "U18") (pin "10") (pinfunction "VIN+_10") (pintype "input"))
    )
    (net (code "92") (name "Net-(U18-VIN-)") (class "Default")
      (node (ref "C119") (pin "2") (pinfunction "2_2") (pintype "passive"))
      (node (ref "R90") (pin "2") (pinfunction "2_2") (pintype "passive"))
      (node (ref "U18") (pin "9") (pinfunction "VIN-_9") (pintype "input"))
    )
    (net (code "93") (name "Net-(U19-ALERT)") (class "Default")
      (node (ref "R107") (pin "2") (pinfunction "2_2") (pintype "passive"))
      (node (ref "U19") (pin "3") (pinfunction "ALERT_3") (pintype "open_collector"))
    )
    (net (code "94") (name "Net-(U19-VIN+)") (class "Default")
      (node (ref "C126") (pin "1") (pinfunction "1_1") (pintype "passive"))
      (node (ref "R105") (pin "2") (pinfunction "2_2") (pintype "passive"))
      (node (ref "U19") (pin "10") (pinfunction "VIN+_10") (pintype "input"))
    )
    (net (code "95") (name "Net-(U19-VIN-)") (class "Default")
      (node (ref "C126") (pin "2") (pinfunction "2_2") (pintype "passive"))
      (node (ref "R103") (pin "2") (pinfunction "2_2") (pintype "passive"))
      (node (ref "U19") (pin "9") (pinfunction "VIN-_9") (pintype "input"))
    )
    (net (code "96") (name "Net-(U20-ALERT)") (class "Default")
      (node (ref "R129") (pin "2") (pinfunction "2_2") (pintype "passive"))
      (node (ref "U20") (pin "3") (pinfunction "ALERT_3") (pintype "open_collector"))
    )
    (net (code "97") (name "TRB_GND") (class "Default")
      (node (ref "C120") (pin "2") (pinfunction "2_2") (pintype "passive"))
      (node (ref "C121") (pin "1") (pinfunction "1_1") (pintype "passive"))
      (node (ref "C122") (pin "1") (pinfunction "1_1") (pintype "passive"))
      (node (ref "C123") (pin "1") (pinfunction "1_1") (pintype "passive"))
      (node (ref "C124") (pin "1") (pinfunction "1_1") (pintype "passive"))
      (node (ref "C125") (pin "1") (pinfunction "1_1") (pintype "passive"))
      (node (ref "C127") (pin "2") (pinfunction "2_2") (pintype "passive"))
      (node (ref "C128") (pin "1") (pinfunction "1_1") (pintype "passive"))
      (node (ref "C129") (pin "1") (pinfunction "1_1") (pintype "passive"))
      (node (ref "C130") (pin "1") (pinfunction "1_1") (pintype "passive"))
      (node (ref "C131") (pin "1") (pinfunction "1_1") (pintype "passive"))
      (node (ref "C132") (pin "1") (pinfunction "1_1") (pintype "passive"))
      (node (ref "C133") (pin "1") (pinfunction "1_1") (pintype "passive"))
      (node (ref "C134") (pin "1") (pinfunction "1_1") (pintype "passive"))
      (node (ref "C135") (pin "1") (pinfunction "1_1") (pintype "passive"))
      (node (ref "C136") (pin "2") (pinfunction "2_2") (pintype "passive"))
      (node (ref "C137") (pin "2") (pinfunction "2_2") (pintype "passive"))
      (node (ref "C138") (pin "2") (pinfunction "2_2") (pintype "passive"))
      (node (ref "C139") (pin "1") (pinfunction "1_1") (pintype "passive"))
      (node (ref "C140") (pin "1") (pinfunction "1_1") (pintype "passive"))
      (node (ref "C141") (pin "1") (pinfunction "1_1") (pintype "passive"))
      (node (ref "C142") (pin "1") (pinfunction "1_1") (pintype "passive"))
      (node (ref "C143") (pin "1") (pinfunction "1_1") (pintype "passive"))
      (node (ref "C144") (pin "2") (pinfunction "2_2") (pintype "passive"))
      (node (ref "C145") (pin "2") (pinfunction "2_2") (pintype "passive"))
      (node (ref "C146") (pin "2") (pinfunction "2_2") (pintype "passive"))
      (node (ref "C147") (pin "2") (pinfunction "2_2") (pintype "passive"))
      (node (ref "C148") (pin "2") (pinfunction "2_2") (pintype "passive"))
      (node (ref "C149") (pin "2") (pinfunction "2_2") (pintype "passive"))
      (node (ref "C150") (pin "2") (pinfunction "2_2") (pintype "passive"))
      (node (ref "C151") (pin "1") (pinfunction "1_1") (pintype "passive"))
      (node (ref "C152") (pin "1") (pinfunction "1_1") (pintype "passive"))
      (node (ref "C153") (pin "1") (pinfunction "1_1") (pintype "passive"))
      (node (ref "C154") (pin "1") (pinfunction "1_1") (pintype "passive"))
      (node (ref "C155") (pin "1") (pinfunction "1_1") (pintype "passive"))
      (node (ref "C156") (pin "1") (pinfunction "1_1") (pintype "passive"))
      (node (ref "C157") (pin "2") (pinfunction "2_2") (pintype "passive"))
      (node (ref "C158") (pin "2") (pinfunction "2_2") (pintype "passive"))
      (node (ref "R100") (pin "1") (pinfunction "1_1") (pintype "passive"))
      (node (ref "R101") (pin "1") (pinfunction "1_1") (pintype "passive"))
      (node (ref "R102") (pin "1") (pinfunction "1_1") (pintype "passive"))
      (node (ref "R108") (pin "1") (pinfunction "1_1") (pintype "passive"))
      (node (ref "R130") (pin "1") (pinfunction "1_1") (pintype "passive"))
      (node (ref "R97") (pin "2") (pinfunction "2_2") (pintype "passive"))
      (node (ref "TP39") (pin "1") (pinfunction "1_1") (pintype "input"))
      (node (ref "U17") (pin "1") (pinfunction "AGND_1") (pintype "passive"))
      (node (ref "U17") (pin "19") (pinfunction "DGND_19") (pintype "passive"))
      (node (ref "U17") (pin "2") (pinfunction "AGND_2") (pintype "passive"))
      (node (ref "U17") (pin "22") (pinfunction "DGND_22") (pintype "passive"))
      (node (ref "U17") (pin "39") (pinfunction "DGND_39") (pintype "passive"))
      (node (ref "U17") (pin "44") (pinfunction "DGND_44") (pintype "passive"))
      (node (ref "U17") (pin "53") (pinfunction "DGND_53") (pintype "passive"))
      (node (ref "U17") (pin "58") (pinfunction "AGND_58") (pintype "passive"))
      (node (ref "U17") (pin "64") (pinfunction "AGND_64") (pintype "passive"))
      (node (ref "U17") (pin "70") (pinfunction "AGND_70") (pintype "passive"))
      (node (ref "U17") (pin "77") (pinfunction "PAD_77") (pintype "passive"))
      (node (ref "U18") (pin "1") (pinfunction "A1_1") (pintype "input"))
      (node (ref "U18") (pin "2") (pinfunction "A0_2") (pintype "input"))
      (node (ref "U18") (pin "7") (pinfunction "GND_7") (pintype "power_in"))
      (node (ref "U19") (pin "7") (pinfunction "GND_7") (pintype "power_in"))
      (node (ref "U20") (pin "2") (pinfunction "GND_2") (pintype "power_in"))
      (node (ref "U20") (pin "4") (pinfunction "ADD0_4") (pintype "input"))
    )
    (net (code "98") (name "unconnected-(U17-OUT0+-Pad57)") (class "Default")
      (node (ref "U17") (pin "57") (pinfunction "OUT0+_57") (pintype "output+no_connect"))
    )
    (net (code "99") (name "unconnected-(U17-OUT0--Pad56)") (class "Default")
      (node (ref "U17") (pin "56") (pinfunction "OUT0-_56") (pintype "output+no_connect"))
    )
    (net (code "100") (name "unconnected-(U17-OUT1+-Pad54)") (class "Default")
      (node (ref "U17") (pin "54") (pinfunction "OUT1+_54") (pintype "output+no_connect"))
    )
    (net (code "101") (name "unconnected-(U17-OUT1--Pad55)") (class "Default")
      (node (ref "U17") (pin "55") (pinfunction "OUT1-_55") (pintype "output+no_connect"))
    )
    (net (code "102") (name "unconnected-(U17-OUT2+-Pad52)") (class "Default")
      (node (ref "U17") (pin "52") (pinfunction "OUT2+_52") (pintype "output+no_connect"))
    )
    (net (code "103") (name "unconnected-(U17-OUT2--Pad51)") (class "Default")
      (node (ref "U17") (pin "51") (pinfunction "OUT2-_51") (pintype "output+no_connect"))
    )
    (net (code "104") (name "unconnected-(U17-OUT3+-Pad49)") (class "Default")
      (node (ref "U17") (pin "49") (pinfunction "OUT3+_49") (pintype "output+no_connect"))
    )
    (net (code "105") (name "unconnected-(U17-OUT3--Pad50)") (class "Default")
      (node (ref "U17") (pin "50") (pinfunction "OUT3-_50") (pintype "output+no_connect"))
    )
    (net (code "106") (name "unconnected-(U17-OUT4+-Pad48)") (class "Default")
      (node (ref "U17") (pin "48") (pinfunction "OUT4+_48") (pintype "output+no_connect"))
    )
    (net (code "107") (name "unconnected-(U17-OUT4--Pad47)") (class "Default")
      (node (ref "U17") (pin "47") (pinfunction "OUT4-_47") (pintype "output+no_connect"))
    )
    (net (code "108") (name "unconnected-(U17-OUT5+-Pad45)") (class "Default")
      (node (ref "U17") (pin "45") (pinfunction "OUT5+_45") (pintype "output+no_connect"))
    )
    (net (code "109") (name "unconnected-(U17-OUT5--Pad46)") (class "Default")
      (node (ref "U17") (pin "46") (pinfunction "OUT5-_46") (pintype "output+no_connect"))
    )
    (net (code "110") (name "unconnected-(U17-OUT6+-Pad42)") (class "Default")
      (node (ref "U17") (pin "42") (pinfunction "OUT6+_42") (pintype "output+no_connect"))
    )
    (net (code "111") (name "unconnected-(U17-OUT6--Pad43)") (class "Default")
      (node (ref "U17") (pin "43") (pinfunction "OUT6-_43") (pintype "output+no_connect"))
    )
    (net (code "112") (name "unconnected-(U17-OUT7+-Pad40)") (class "Default")
      (node (ref "U17") (pin "40") (pinfunction "OUT7+_40") (pintype "output+no_connect"))
    )
    (net (code "113") (name "unconnected-(U17-OUT7--Pad41)") (class "Default")
      (node (ref "U17") (pin "41") (pinfunction "OUT7-_41") (pintype "output+no_connect"))
    )
  )
)
